# Edzzanine_Console.net
KiCad netlist of a schematic drawn in EAGLE
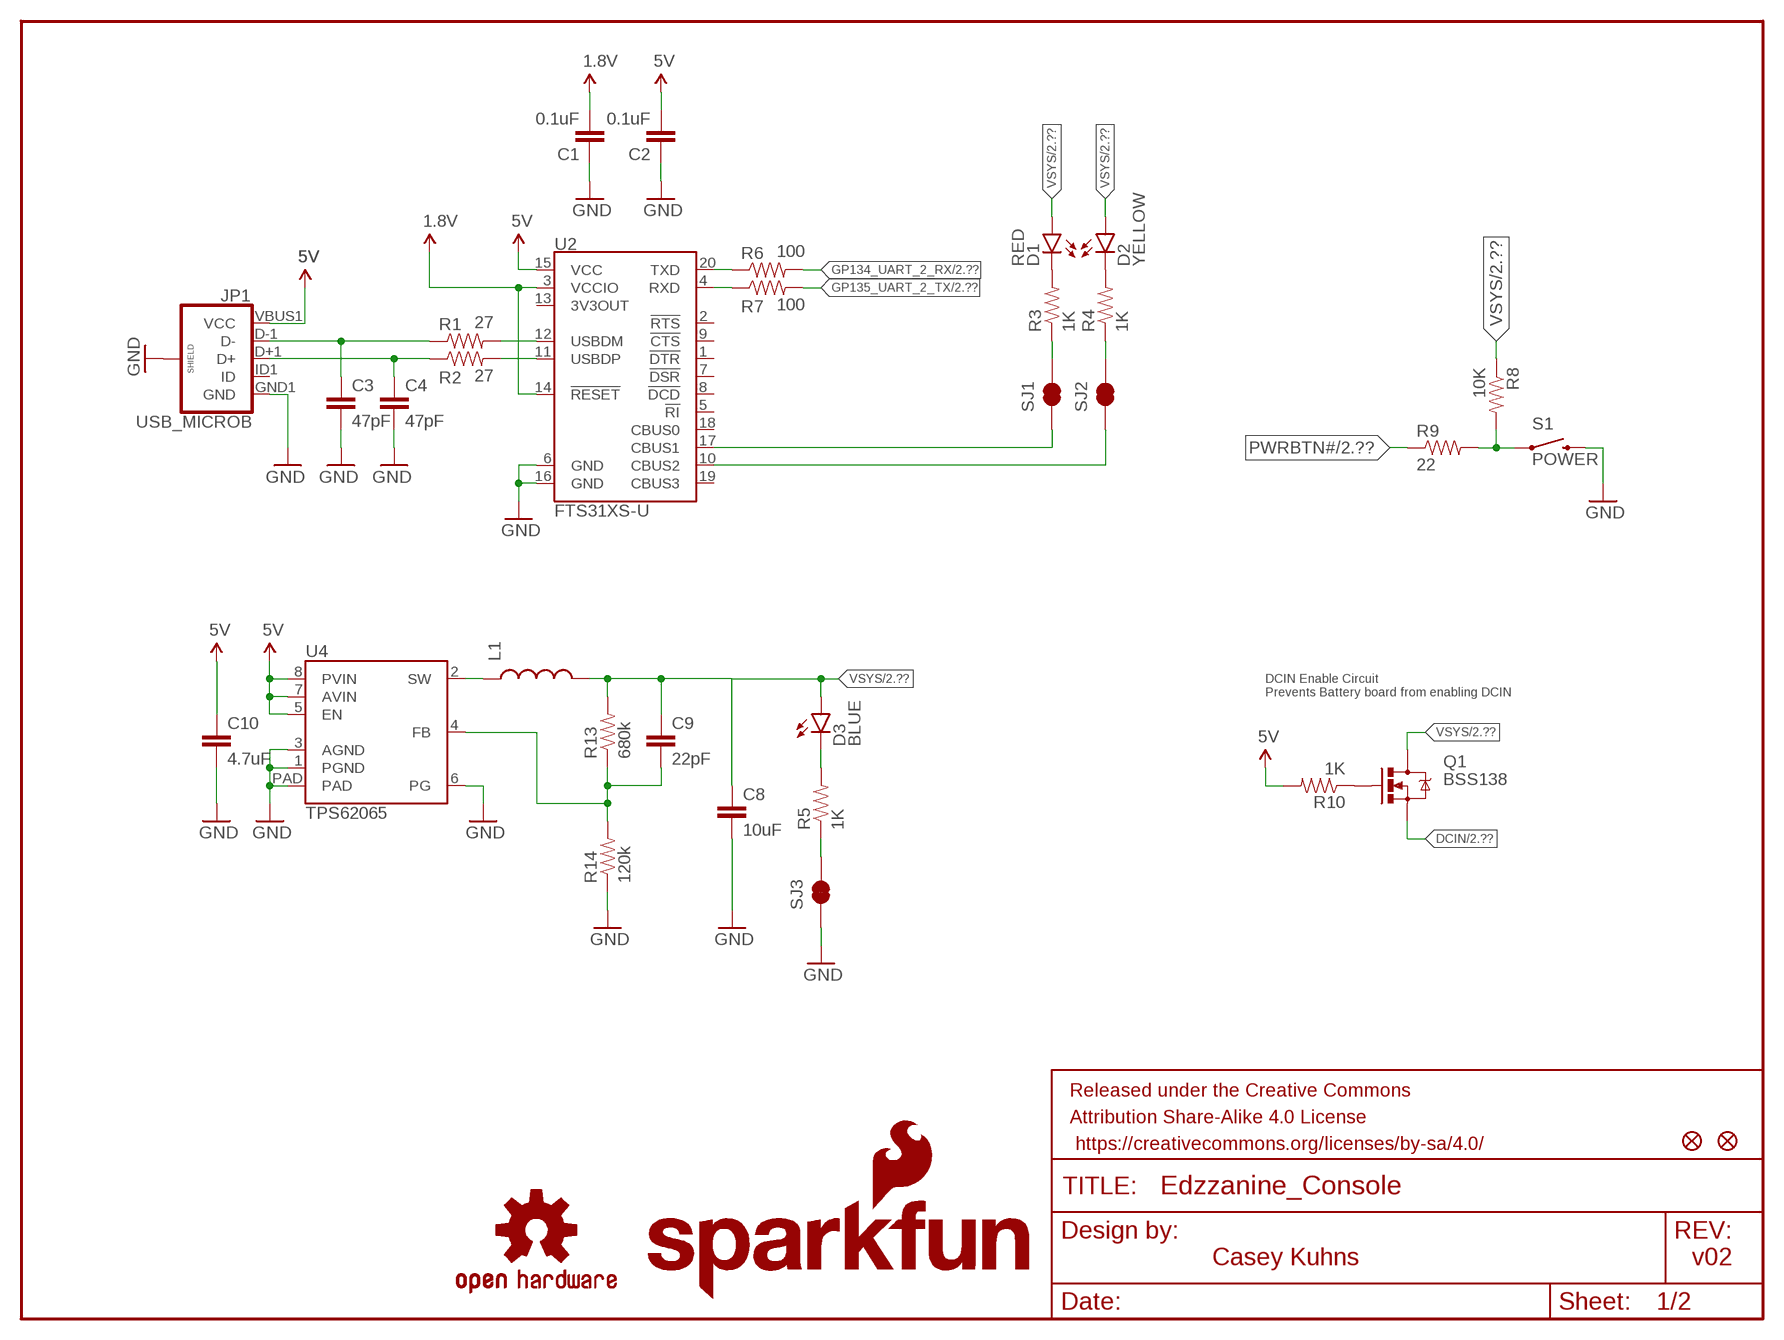
[diagram p0: schematic, sheet 1]
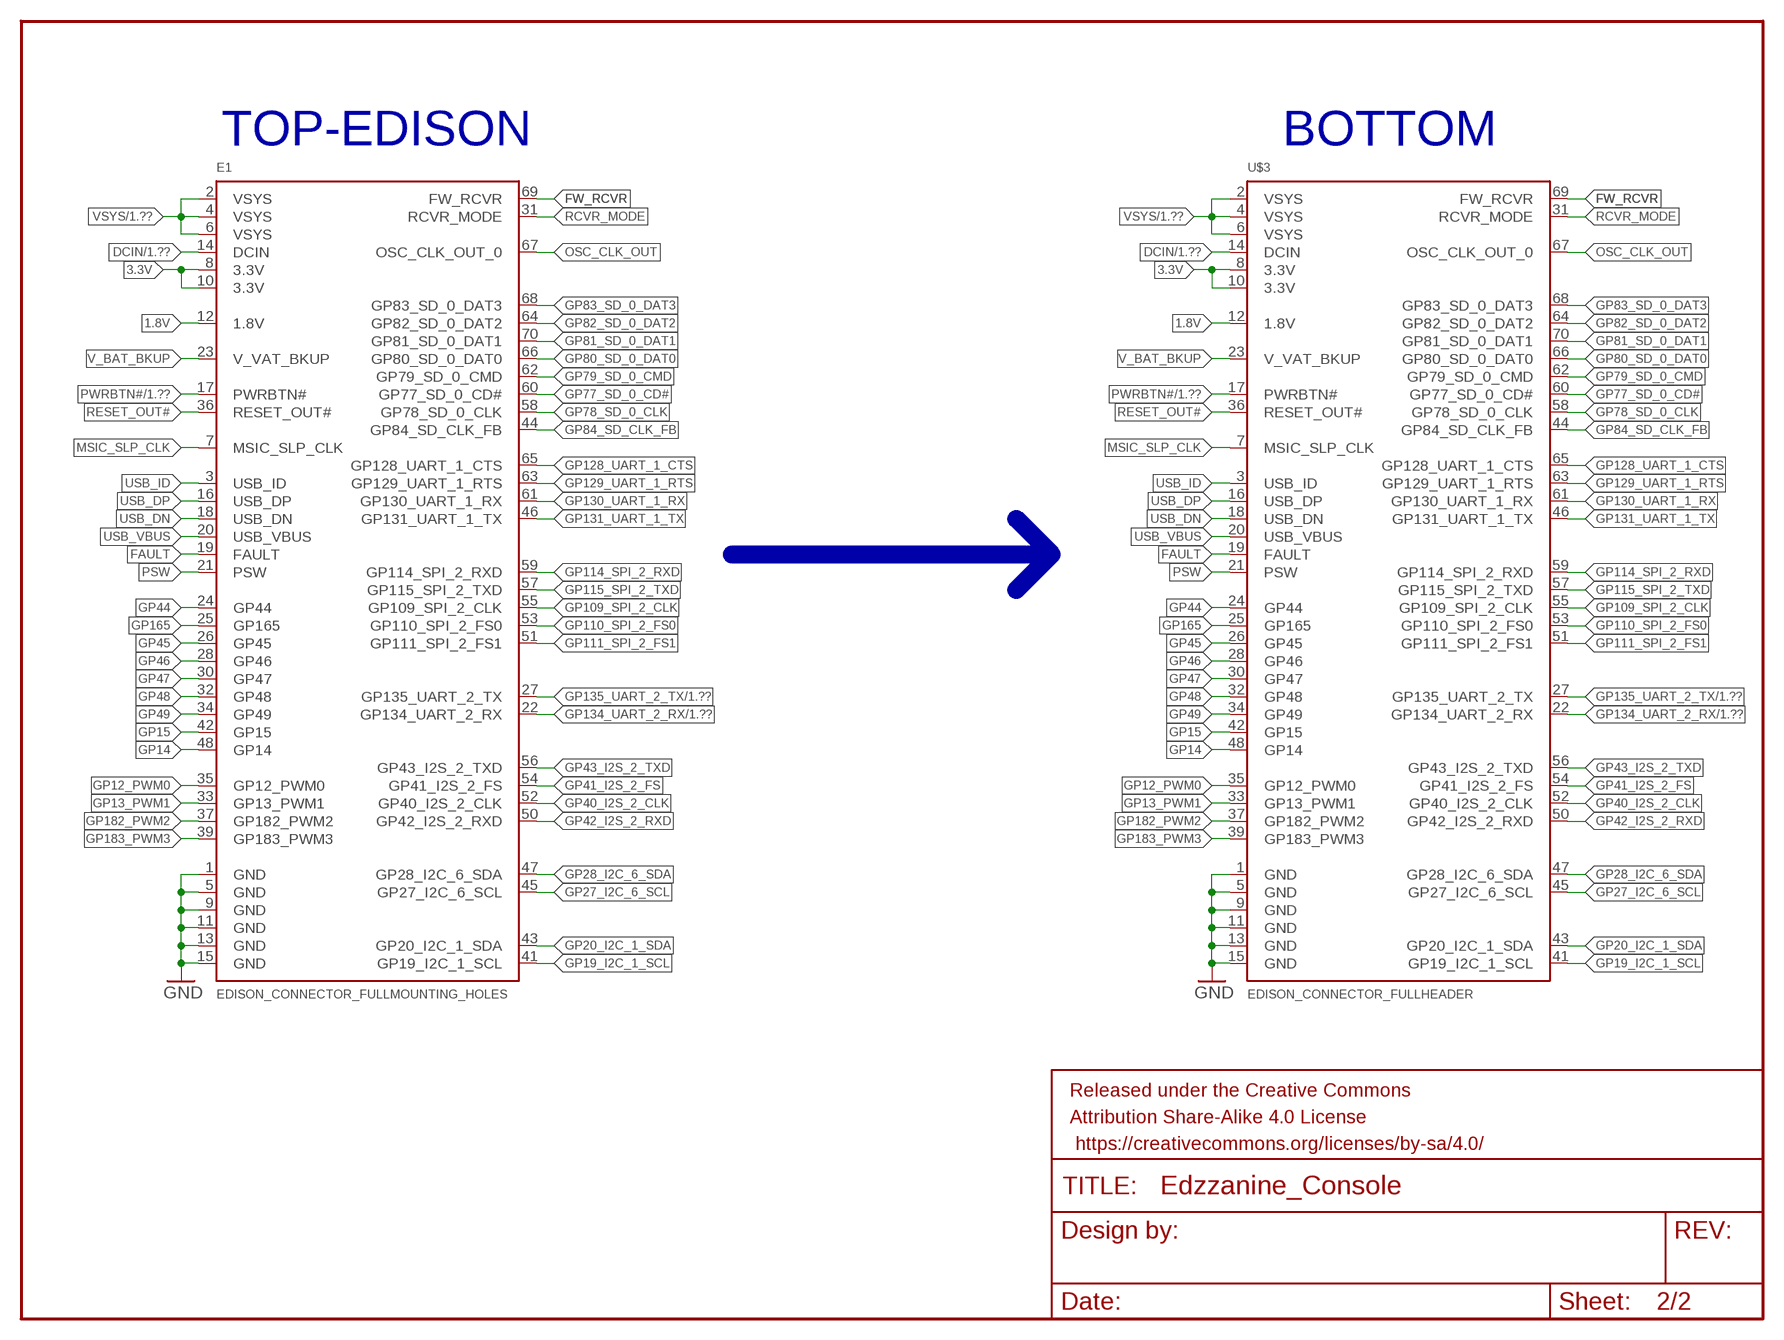
[diagram p1: schematic, sheet 2]

(export (version "E")
  (design (tool "Eeschema 10.0.6"))
  (components
    (comp (ref "E1")
      (value "EDISON_CONNECTOR_FULLMOUNTING_HOLES")
      (footprint "eagle-import:EDISON_DAUGHTER")
      (libsource (lib "eagle-import") (part "EDISON_CONNECTOR_FULLMOUNTING_HOLES"))
    )
    (comp (ref "FRAME2")
      (value "FRAME-LETTER")
      (footprint "eagle-import:CREATIVE_COMMONS")
      (libsource (lib "eagle-import") (part "FRAME-LETTER"))
    )
    (comp (ref "U$3")
      (value "EDISON_CONNECTOR_FULLHEADER")
      (footprint "eagle-import:DF40C-70DP-0.4(51)")
      (libsource (lib "eagle-import") (part "EDISON_CONNECTOR_FULLHEADER"))
    )
    (comp (ref "C1")
      (value "0.1uF")
      (footprint "eagle-import:0603-CAP")
      (libsource (lib "eagle-import") (part "0.1UF-25V-5%(0603)"))
    )
    (comp (ref "C2")
      (value "0.1uF")
      (footprint "eagle-import:0603-CAP")
      (libsource (lib "eagle-import") (part "0.1UF-25V-5%(0603)"))
    )
    (comp (ref "C3")
      (value "47pF")
      (footprint "eagle-import:0603-CAP")
      (libsource (lib "eagle-import") (part "47PF-50V-5%(0603)"))
    )
    (comp (ref "C4")
      (value "47pF")
      (footprint "eagle-import:0603-CAP")
      (libsource (lib "eagle-import") (part "47PF-50V-5%(0603)"))
    )
    (comp (ref "C8")
      (value "10uF")
      (footprint "eagle-import:1206")
      (libsource (lib "eagle-import") (part "10UF-6.3V-20%(1206)"))
    )
    (comp (ref "C9")
      (value "22pF")
      (footprint "eagle-import:0603-CAP")
      (libsource (lib "eagle-import") (part "22PF-50V-5%(0603)"))
    )
    (comp (ref "C10")
      (value "4.7uF")
      (footprint "eagle-import:0603-CAP")
      (libsource (lib "eagle-import") (part "4.7UF-6.3V-10%(0603)0603"))
    )
    (comp (ref "D1")
      (value "RED")
      (footprint "eagle-import:LED-0603")
      (libsource (lib "eagle-import") (part "LED-RED0603"))
    )
    (comp (ref "D2")
      (value "YELLOW")
      (footprint "eagle-import:LED-0603")
      (libsource (lib "eagle-import") (part "LED-YELLOW0603"))
    )
    (comp (ref "D3")
      (value "BLUE")
      (footprint "eagle-import:LED-0603")
      (libsource (lib "eagle-import") (part "LED-BLUE0603"))
    )
    (comp (ref "FID1")
      (value "FIDUCIAL1X2")
      (footprint "eagle-import:FIDUCIAL-1X2")
      (libsource (lib "eagle-import") (part "FIDUCIAL1X2"))
    )
    (comp (ref "FID2")
      (value "FIDUCIAL1X2")
      (footprint "eagle-import:FIDUCIAL-1X2")
      (libsource (lib "eagle-import") (part "FIDUCIAL1X2"))
    )
    (comp (ref "FRAME1")
      (value "FRAME-LETTER")
      (footprint "eagle-import:CREATIVE_COMMONS")
      (libsource (lib "eagle-import") (part "FRAME-LETTER"))
    )
    (comp (ref "JP1")
      (value "USB_MICROB")
      (footprint "eagle-import:USB-B-MICRO-SMD_V03")
      (libsource (lib "eagle-import") (part "USB_MICROB_PLUGCONN-11752"))
    )
    (comp (ref "L1")
      (value "INDUCTOR")
      (footprint "eagle-import:INDUCTOR-SRP4020")
      (libsource (lib "eagle-import") (part "INDUCTOR"))
    )
    (comp (ref "LOGO1")
      (value "SFE_LOGO_NAME_FLAME.1_INCH")
      (footprint "eagle-import:SFE_LOGO_NAME_FLAME_.1")
      (libsource (lib "eagle-import") (part "SFE_LOGO_NAME_FLAME.1_INCH"))
    )
    (comp (ref "LOGO4")
      (value "OSHW-LOGOS")
      (footprint "eagle-import:OSHW-LOGO-S")
      (libsource (lib "eagle-import") (part "OSHW-LOGOS"))
    )
    (comp (ref "Q1")
      (value "BSS138")
      (footprint "eagle-import:SOT23-3")
      (libsource (lib "eagle-import") (part "MOSFET-NCHANNELBSS138"))
    )
    (comp (ref "R1")
      (value "27")
      (footprint "eagle-import:0603")
      (libsource (lib "eagle-import") (part "27OHM1/10W1%(0603)"))
    )
    (comp (ref "R2")
      (value "27")
      (footprint "eagle-import:0603")
      (libsource (lib "eagle-import") (part "27OHM1/10W1%(0603)"))
    )
    (comp (ref "R3")
      (value "1K")
      (footprint "eagle-import:0603-RES")
      (libsource (lib "eagle-import") (part "1KOHM1/10W1%(0603)"))
    )
    (comp (ref "R4")
      (value "1K")
      (footprint "eagle-import:0603-RES")
      (libsource (lib "eagle-import") (part "1KOHM1/10W1%(0603)"))
    )
    (comp (ref "R5")
      (value "1K")
      (footprint "eagle-import:0603-RES")
      (libsource (lib "eagle-import") (part "1KOHM1/10W1%(0603)"))
    )
    (comp (ref "R6")
      (value "100")
      (footprint "eagle-import:0603-RES")
      (libsource (lib "eagle-import") (part "100OHM1/10W1%(0603)"))
    )
    (comp (ref "R7")
      (value "100")
      (footprint "eagle-import:0603-RES")
      (libsource (lib "eagle-import") (part "100OHM1/10W1%(0603)"))
    )
    (comp (ref "R8")
      (value "10K")
      (footprint "eagle-import:0603-RES")
      (libsource (lib "eagle-import") (part "10KOHM1/10W1%(0603)0603"))
    )
    (comp (ref "R9")
      (value "22")
      (footprint "eagle-import:0603-RES")
      (libsource (lib "eagle-import") (part "22OHM1/10W1%(0603)"))
    )
    (comp (ref "R10")
      (value "1K")
      (footprint "eagle-import:0603-RES")
      (libsource (lib "eagle-import") (part "1KOHM1/10W1%(0603)"))
    )
    (comp (ref "R13")
      (value "680k")
      (footprint "eagle-import:0603-RES")
      (libsource (lib "eagle-import") (part "RESISTOR0603"))
    )
    (comp (ref "R14")
      (value "120k")
      (footprint "eagle-import:0603-RES")
      (libsource (lib "eagle-import") (part "RESISTOR0603"))
    )
    (comp (ref "S1")
      (value "POWER")
      (footprint "eagle-import:TACTILE_SWITCH-SMD-RIGHT-ANGLE")
      (libsource (lib "eagle-import") (part "SWITCH-MOMENTARY-2TACTILE-SWITCH-SMD-RIGHT-ANGLE"))
    )
    (comp (ref "SJ1")
      (value "JUMPER-PAD-2-NC_BY_TRACE")
      (footprint "eagle-import:PAD-JUMPER-2-NC_BY_TRACE_YES_SILK")
      (libsource (lib "eagle-import") (part "JUMPER-PAD-2-NC_BY_TRACE"))
    )
    (comp (ref "SJ2")
      (value "JUMPER-PAD-2-NC_BY_TRACE")
      (footprint "eagle-import:PAD-JUMPER-2-NC_BY_TRACE_YES_SILK")
      (libsource (lib "eagle-import") (part "JUMPER-PAD-2-NC_BY_TRACE"))
    )
    (comp (ref "SJ3")
      (value "JUMPER-PAD-2-NC_BY_TRACE")
      (footprint "eagle-import:PAD-JUMPER-2-NC_BY_TRACE_YES_SILK")
      (libsource (lib "eagle-import") (part "JUMPER-PAD-2-NC_BY_TRACE"))
    )
    (comp (ref "U2")
      (value "FTS31XS-U")
      (footprint "eagle-import:SSOP20_L")
      (libsource (lib "eagle-import") (part "FT231XS"))
    )
    (comp (ref "U4")
      (value "TPS62065")
      (footprint "eagle-import:WSON-8-PAD")
      (libsource (lib "eagle-import") (part "TPS62065"))
    )
  )
  (nets
    (net (code "1") (name "1.8V") (class "Default")
      (node (ref "C1") (pin "2") (pinfunction "2_2") (pintype "passive"))
      (node (ref "E1") (pin "12") (pinfunction "1.8V_12") (pintype "bidirectional"))
      (node (ref "U$3") (pin "12") (pinfunction "1.8V_12") (pintype "bidirectional"))
      (node (ref "U2") (pin "14") (pinfunction "~{RESET}_14") (pintype "bidirectional"))
      (node (ref "U2") (pin "3") (pinfunction "VCCIO_3") (pintype "bidirectional"))
    )
    (net (code "2") (name "3.3V") (class "Default")
      (node (ref "E1") (pin "10") (pinfunction "3.3V_10") (pintype "bidirectional"))
      (node (ref "E1") (pin "8") (pinfunction "3.3V_8") (pintype "bidirectional"))
      (node (ref "U$3") (pin "10") (pinfunction "3.3V_10") (pintype "bidirectional"))
      (node (ref "U$3") (pin "8") (pinfunction "3.3V_8") (pintype "bidirectional"))
    )
    (net (code "3") (name "5V") (class "Default")
      (node (ref "C10") (pin "1") (pinfunction "1_1") (pintype "passive"))
      (node (ref "C2") (pin "2") (pinfunction "2_2") (pintype "passive"))
      (node (ref "JP1") (pin "VBUS1") (pinfunction "VCC_VBUS1") (pintype "bidirectional"))
      (node (ref "R10") (pin "2") (pinfunction "2_2") (pintype "passive"))
      (node (ref "U2") (pin "15") (pinfunction "VCC_15") (pintype "bidirectional"))
      (node (ref "U4") (pin "5") (pinfunction "EN_5") (pintype "bidirectional"))
      (node (ref "U4") (pin "7") (pinfunction "AVIN_7") (pintype "bidirectional"))
      (node (ref "U4") (pin "8") (pinfunction "PVIN_8") (pintype "bidirectional"))
    )
    (net (code "4") (name "DCIN") (class "Default")
      (node (ref "E1") (pin "14") (pinfunction "DCIN_14") (pintype "bidirectional"))
      (node (ref "Q1") (pin "2") (pinfunction "S_2") (pintype "passive"))
      (node (ref "U$3") (pin "14") (pinfunction "DCIN_14") (pintype "bidirectional"))
    )
    (net (code "5") (name "FAULT") (class "Default")
      (node (ref "E1") (pin "19") (pinfunction "FAULT_19") (pintype "bidirectional"))
      (node (ref "U$3") (pin "19") (pinfunction "FAULT_19") (pintype "bidirectional"))
    )
    (net (code "6") (name "FW_RCVR") (class "Default")
      (node (ref "E1") (pin "69") (pinfunction "FW_RCVR_69") (pintype "bidirectional"))
      (node (ref "U$3") (pin "69") (pinfunction "FW_RCVR_69") (pintype "bidirectional"))
    )
    (net (code "7") (name "GND") (class "Default")
      (node (ref "C1") (pin "1") (pinfunction "1_1") (pintype "passive"))
      (node (ref "C10") (pin "2") (pinfunction "2_2") (pintype "passive"))
      (node (ref "C2") (pin "1") (pinfunction "1_1") (pintype "passive"))
      (node (ref "C3") (pin "2") (pinfunction "2_2") (pintype "passive"))
      (node (ref "C4") (pin "2") (pinfunction "2_2") (pintype "passive"))
      (node (ref "C8") (pin "2") (pinfunction "2_2") (pintype "passive"))
      (node (ref "E1") (pin "1") (pinfunction "GND_1") (pintype "bidirectional"))
      (node (ref "E1") (pin "11") (pinfunction "GND_11") (pintype "bidirectional"))
      (node (ref "E1") (pin "13") (pinfunction "GND_13") (pintype "bidirectional"))
      (node (ref "E1") (pin "15") (pinfunction "GND_15") (pintype "bidirectional"))
      (node (ref "E1") (pin "5") (pinfunction "GND_5") (pintype "bidirectional"))
      (node (ref "E1") (pin "9") (pinfunction "GND_9") (pintype "bidirectional"))
      (node (ref "JP1") (pin "GND1") (pinfunction "GND_GND1") (pintype "bidirectional"))
      (node (ref "JP1") (pin "SHIELD1") (pinfunction "SHIELD_SHIELD1") (pintype "bidirectional"))
      (node (ref "JP1") (pin "SHIELD2") (pinfunction "SHIELD_SHIELD2") (pintype "bidirectional"))
      (node (ref "JP1") (pin "SHIELD3") (pinfunction "SHIELD_SHIELD3") (pintype "bidirectional"))
      (node (ref "R14") (pin "1") (pinfunction "1_1") (pintype "passive"))
      (node (ref "S1") (pin "2") (pinfunction "2_2") (pintype "passive"))
      (node (ref "SJ3") (pin "1") (pinfunction "1_1") (pintype "passive"))
      (node (ref "U$3") (pin "1") (pinfunction "GND_1") (pintype "bidirectional"))
      (node (ref "U$3") (pin "11") (pinfunction "GND_11") (pintype "bidirectional"))
      (node (ref "U$3") (pin "13") (pinfunction "GND_13") (pintype "bidirectional"))
      (node (ref "U$3") (pin "15") (pinfunction "GND_15") (pintype "bidirectional"))
      (node (ref "U$3") (pin "5") (pinfunction "GND_5") (pintype "bidirectional"))
      (node (ref "U$3") (pin "9") (pinfunction "GND_9") (pintype "bidirectional"))
      (node (ref "U2") (pin "16") (pinfunction "GND_16") (pintype "bidirectional"))
      (node (ref "U2") (pin "6") (pinfunction "GND_6") (pintype "bidirectional"))
      (node (ref "U4") (pin "1") (pinfunction "PGND_1") (pintype "bidirectional"))
      (node (ref "U4") (pin "3") (pinfunction "AGND_3") (pintype "bidirectional"))
      (node (ref "U4") (pin "6") (pinfunction "PG_6") (pintype "bidirectional"))
      (node (ref "U4") (pin "PAD") (pinfunction "PAD_PAD") (pintype "bidirectional"))
    )
    (net (code "8") (name "GP12_PWM0") (class "Default")
      (node (ref "E1") (pin "35") (pinfunction "GP12_PWM0_35") (pintype "bidirectional"))
      (node (ref "U$3") (pin "35") (pinfunction "GP12_PWM0_35") (pintype "bidirectional"))
    )
    (net (code "9") (name "GP13_PWM1") (class "Default")
      (node (ref "E1") (pin "33") (pinfunction "GP13_PWM1_33") (pintype "bidirectional"))
      (node (ref "U$3") (pin "33") (pinfunction "GP13_PWM1_33") (pintype "bidirectional"))
    )
    (net (code "10") (name "GP14") (class "Default")
      (node (ref "E1") (pin "48") (pinfunction "GP14_48") (pintype "bidirectional"))
      (node (ref "U$3") (pin "48") (pinfunction "GP14_48") (pintype "bidirectional"))
    )
    (net (code "11") (name "GP15") (class "Default")
      (node (ref "E1") (pin "42") (pinfunction "GP15_42") (pintype "bidirectional"))
      (node (ref "U$3") (pin "42") (pinfunction "GP15_42") (pintype "bidirectional"))
    )
    (net (code "12") (name "GP19_I2C_1_SCL") (class "Default")
      (node (ref "E1") (pin "41") (pinfunction "GP19_I2C_1_SCL_41") (pintype "bidirectional"))
      (node (ref "U$3") (pin "41") (pinfunction "GP19_I2C_1_SCL_41") (pintype "bidirectional"))
    )
    (net (code "13") (name "GP20_I2C_1_SDA") (class "Default")
      (node (ref "E1") (pin "43") (pinfunction "GP20_I2C_1_SDA_43") (pintype "bidirectional"))
      (node (ref "U$3") (pin "43") (pinfunction "GP20_I2C_1_SDA_43") (pintype "bidirectional"))
    )
    (net (code "14") (name "GP27_I2C_6_SCL") (class "Default")
      (node (ref "E1") (pin "45") (pinfunction "GP27_I2C_6_SCL_45") (pintype "bidirectional"))
      (node (ref "U$3") (pin "45") (pinfunction "GP27_I2C_6_SCL_45") (pintype "bidirectional"))
    )
    (net (code "15") (name "GP28_I2C_6_SDA") (class "Default")
      (node (ref "E1") (pin "47") (pinfunction "GP28_I2C_6_SDA_47") (pintype "bidirectional"))
      (node (ref "U$3") (pin "47") (pinfunction "GP28_I2C_6_SDA_47") (pintype "bidirectional"))
    )
    (net (code "16") (name "GP40_I2S_2_CLK") (class "Default")
      (node (ref "E1") (pin "52") (pinfunction "GP40_I2S_2_CLK_52") (pintype "bidirectional"))
      (node (ref "U$3") (pin "52") (pinfunction "GP40_I2S_2_CLK_52") (pintype "bidirectional"))
    )
    (net (code "17") (name "GP41_I2S_2_FS") (class "Default")
      (node (ref "E1") (pin "54") (pinfunction "GP41_I2S_2_FS_54") (pintype "bidirectional"))
      (node (ref "U$3") (pin "54") (pinfunction "GP41_I2S_2_FS_54") (pintype "bidirectional"))
    )
    (net (code "18") (name "GP42_I2S_2_RXD") (class "Default")
      (node (ref "E1") (pin "50") (pinfunction "GP42_I2S_2_RXD_50") (pintype "bidirectional"))
      (node (ref "U$3") (pin "50") (pinfunction "GP42_I2S_2_RXD_50") (pintype "bidirectional"))
    )
    (net (code "19") (name "GP43_I2S_2_TXD") (class "Default")
      (node (ref "E1") (pin "56") (pinfunction "GP43_I2S_2_TXD_56") (pintype "bidirectional"))
      (node (ref "U$3") (pin "56") (pinfunction "GP43_I2S_2_TXD_56") (pintype "bidirectional"))
    )
    (net (code "20") (name "GP44") (class "Default")
      (node (ref "E1") (pin "24") (pinfunction "GP44_24") (pintype "bidirectional"))
      (node (ref "U$3") (pin "24") (pinfunction "GP44_24") (pintype "bidirectional"))
    )
    (net (code "21") (name "GP45") (class "Default")
      (node (ref "E1") (pin "26") (pinfunction "GP45_26") (pintype "bidirectional"))
      (node (ref "U$3") (pin "26") (pinfunction "GP45_26") (pintype "bidirectional"))
    )
    (net (code "22") (name "GP46") (class "Default")
      (node (ref "E1") (pin "28") (pinfunction "GP46_28") (pintype "bidirectional"))
      (node (ref "U$3") (pin "28") (pinfunction "GP46_28") (pintype "bidirectional"))
    )
    (net (code "23") (name "GP47") (class "Default")
      (node (ref "E1") (pin "30") (pinfunction "GP47_30") (pintype "bidirectional"))
      (node (ref "U$3") (pin "30") (pinfunction "GP47_30") (pintype "bidirectional"))
    )
    (net (code "24") (name "GP48") (class "Default")
      (node (ref "E1") (pin "32") (pinfunction "GP48_32") (pintype "bidirectional"))
      (node (ref "U$3") (pin "32") (pinfunction "GP48_32") (pintype "bidirectional"))
    )
    (net (code "25") (name "GP49") (class "Default")
      (node (ref "E1") (pin "34") (pinfunction "GP49_34") (pintype "bidirectional"))
      (node (ref "U$3") (pin "34") (pinfunction "GP49_34") (pintype "bidirectional"))
    )
    (net (code "26") (name "GP77_SD_0_CD#") (class "Default")
      (node (ref "E1") (pin "60") (pinfunction "GP77_SD_0_CD#_60") (pintype "bidirectional"))
      (node (ref "U$3") (pin "60") (pinfunction "GP77_SD_0_CD#_60") (pintype "bidirectional"))
    )
    (net (code "27") (name "GP78_SD_0_CLK") (class "Default")
      (node (ref "E1") (pin "58") (pinfunction "GP78_SD_0_CLK_58") (pintype "bidirectional"))
      (node (ref "U$3") (pin "58") (pinfunction "GP78_SD_0_CLK_58") (pintype "bidirectional"))
    )
    (net (code "28") (name "GP79_SD_0_CMD") (class "Default")
      (node (ref "E1") (pin "62") (pinfunction "GP79_SD_0_CMD_62") (pintype "bidirectional"))
      (node (ref "U$3") (pin "62") (pinfunction "GP79_SD_0_CMD_62") (pintype "bidirectional"))
    )
    (net (code "29") (name "GP80_SD_0_DAT0") (class "Default")
      (node (ref "E1") (pin "66") (pinfunction "GP80_SD_0_DAT0_66") (pintype "bidirectional"))
      (node (ref "U$3") (pin "66") (pinfunction "GP80_SD_0_DAT0_66") (pintype "bidirectional"))
    )
    (net (code "30") (name "GP81_SD_0_DAT1") (class "Default")
      (node (ref "E1") (pin "70") (pinfunction "GP81_SD_0_DAT1_70") (pintype "bidirectional"))
      (node (ref "U$3") (pin "70") (pinfunction "GP81_SD_0_DAT1_70") (pintype "bidirectional"))
    )
    (net (code "31") (name "GP82_SD_0_DAT2") (class "Default")
      (node (ref "E1") (pin "64") (pinfunction "GP82_SD_0_DAT2_64") (pintype "bidirectional"))
      (node (ref "U$3") (pin "64") (pinfunction "GP82_SD_0_DAT2_64") (pintype "bidirectional"))
    )
    (net (code "32") (name "GP83_SD_0_DAT3") (class "Default")
      (node (ref "E1") (pin "68") (pinfunction "GP83_SD_0_DAT3_68") (pintype "bidirectional"))
      (node (ref "U$3") (pin "68") (pinfunction "GP83_SD_0_DAT3_68") (pintype "bidirectional"))
    )
    (net (code "33") (name "GP84_SD_CLK_FB") (class "Default")
      (node (ref "E1") (pin "44") (pinfunction "GP84_SD_CLK_FB_44") (pintype "bidirectional"))
      (node (ref "U$3") (pin "44") (pinfunction "GP84_SD_CLK_FB_44") (pintype "bidirectional"))
    )
    (net (code "34") (name "GP109_SPI_2_CLK") (class "Default")
      (node (ref "E1") (pin "55") (pinfunction "GP109_SPI_2_CLK_55") (pintype "bidirectional"))
      (node (ref "U$3") (pin "55") (pinfunction "GP109_SPI_2_CLK_55") (pintype "bidirectional"))
    )
    (net (code "35") (name "GP110_SPI_2_FS0") (class "Default")
      (node (ref "E1") (pin "53") (pinfunction "GP110_SPI_2_FS0_53") (pintype "bidirectional"))
      (node (ref "U$3") (pin "53") (pinfunction "GP110_SPI_2_FS0_53") (pintype "bidirectional"))
    )
    (net (code "36") (name "GP111_SPI_2_FS1") (class "Default")
      (node (ref "E1") (pin "51") (pinfunction "GP111_SPI_2_FS1_51") (pintype "bidirectional"))
      (node (ref "U$3") (pin "51") (pinfunction "GP111_SPI_2_FS1_51") (pintype "bidirectional"))
    )
    (net (code "37") (name "GP114_SPI_2_RXD") (class "Default")
      (node (ref "E1") (pin "59") (pinfunction "GP114_SPI_2_RXD_59") (pintype "bidirectional"))
      (node (ref "U$3") (pin "59") (pinfunction "GP114_SPI_2_RXD_59") (pintype "bidirectional"))
    )
    (net (code "38") (name "GP115_SPI_2_TXD") (class "Default")
      (node (ref "E1") (pin "57") (pinfunction "GP115_SPI_2_TXD_57") (pintype "bidirectional"))
      (node (ref "U$3") (pin "57") (pinfunction "GP115_SPI_2_TXD_57") (pintype "bidirectional"))
    )
    (net (code "39") (name "GP128_UART_1_CTS") (class "Default")
      (node (ref "E1") (pin "65") (pinfunction "GP128_UART_1_CTS_65") (pintype "bidirectional"))
      (node (ref "U$3") (pin "65") (pinfunction "GP128_UART_1_CTS_65") (pintype "bidirectional"))
    )
    (net (code "40") (name "GP129_UART_1_RTS") (class "Default")
      (node (ref "E1") (pin "63") (pinfunction "GP129_UART_1_RTS_63") (pintype "bidirectional"))
      (node (ref "U$3") (pin "63") (pinfunction "GP129_UART_1_RTS_63") (pintype "bidirectional"))
    )
    (net (code "41") (name "GP130_UART_1_RX") (class "Default")
      (node (ref "E1") (pin "61") (pinfunction "GP130_UART_1_RX_61") (pintype "bidirectional"))
      (node (ref "U$3") (pin "61") (pinfunction "GP130_UART_1_RX_61") (pintype "bidirectional"))
    )
    (net (code "42") (name "GP131_UART_1_TX") (class "Default")
      (node (ref "E1") (pin "46") (pinfunction "GP131_UART_1_TX_46") (pintype "bidirectional"))
      (node (ref "U$3") (pin "46") (pinfunction "GP131_UART_1_TX_46") (pintype "bidirectional"))
    )
    (net (code "43") (name "GP134_UART_2_RX") (class "Default")
      (node (ref "E1") (pin "22") (pinfunction "GP134_UART_2_RX_22") (pintype "bidirectional"))
      (node (ref "R6") (pin "2") (pinfunction "2_2") (pintype "passive"))
      (node (ref "U$3") (pin "22") (pinfunction "GP134_UART_2_RX_22") (pintype "bidirectional"))
    )
    (net (code "44") (name "GP135_UART_2_TX") (class "Default")
      (node (ref "E1") (pin "27") (pinfunction "GP135_UART_2_TX_27") (pintype "bidirectional"))
      (node (ref "R7") (pin "2") (pinfunction "2_2") (pintype "passive"))
      (node (ref "U$3") (pin "27") (pinfunction "GP135_UART_2_TX_27") (pintype "bidirectional"))
    )
    (net (code "45") (name "GP165") (class "Default")
      (node (ref "E1") (pin "25") (pinfunction "GP165_25") (pintype "bidirectional"))
      (node (ref "U$3") (pin "25") (pinfunction "GP165_25") (pintype "bidirectional"))
    )
    (net (code "46") (name "GP182_PWM2") (class "Default")
      (node (ref "E1") (pin "37") (pinfunction "GP182_PWM2_37") (pintype "bidirectional"))
      (node (ref "U$3") (pin "37") (pinfunction "GP182_PWM2_37") (pintype "bidirectional"))
    )
    (net (code "47") (name "GP183_PWM3") (class "Default")
      (node (ref "E1") (pin "39") (pinfunction "GP183_PWM3_39") (pintype "bidirectional"))
      (node (ref "U$3") (pin "39") (pinfunction "GP183_PWM3_39") (pintype "bidirectional"))
    )
    (net (code "48") (name "MSIC_SLP_CLK") (class "Default")
      (node (ref "E1") (pin "7") (pinfunction "MSIC_SLP_CLK_7") (pintype "bidirectional"))
      (node (ref "U$3") (pin "7") (pinfunction "MSIC_SLP_CLK_7") (pintype "bidirectional"))
    )
    (net (code "49") (name "Net-(D1-PadC)") (class "Default")
      (node (ref "D1") (pin "C") (pinfunction "C_C") (pintype "passive"))
      (node (ref "R3") (pin "2") (pinfunction "2_2") (pintype "passive"))
    )
    (net (code "50") (name "Net-(D2-PadC)") (class "Default")
      (node (ref "D2") (pin "C") (pinfunction "C_C") (pintype "passive"))
      (node (ref "R4") (pin "2") (pinfunction "2_2") (pintype "passive"))
    )
    (net (code "51") (name "Net-(D3-PadC)") (class "Default")
      (node (ref "D3") (pin "C") (pinfunction "C_C") (pintype "passive"))
      (node (ref "R5") (pin "2") (pinfunction "2_2") (pintype "passive"))
    )
    (net (code "52") (name "Net-(JP1-D+)") (class "Default")
      (node (ref "C4") (pin "1") (pinfunction "1_1") (pintype "passive"))
      (node (ref "JP1") (pin "D+1") (pinfunction "D+_D+1") (pintype "bidirectional"))
      (node (ref "R2") (pin "1") (pinfunction "1_1") (pintype "passive"))
    )
    (net (code "53") (name "Net-(JP1-D-)") (class "Default")
      (node (ref "C3") (pin "1") (pinfunction "1_1") (pintype "passive"))
      (node (ref "JP1") (pin "D-1") (pinfunction "D-_D-1") (pintype "bidirectional"))
      (node (ref "R1") (pin "1") (pinfunction "1_1") (pintype "passive"))
    )
    (net (code "54") (name "Net-(L1-1)") (class "Default")
      (node (ref "L1") (pin "P$1") (pinfunction "1_P$1") (pintype "passive"))
      (node (ref "U4") (pin "2") (pinfunction "SW_2") (pintype "bidirectional"))
    )
    (net (code "55") (name "Net-(Q1-G)") (class "Default")
      (node (ref "Q1") (pin "1") (pinfunction "G_1") (pintype "passive"))
      (node (ref "R10") (pin "1") (pinfunction "1_1") (pintype "passive"))
    )
    (net (code "56") (name "Net-(R3-Pad1)") (class "Default")
      (node (ref "R3") (pin "1") (pinfunction "1_1") (pintype "passive"))
      (node (ref "SJ1") (pin "2") (pinfunction "2_2") (pintype "passive"))
    )
    (net (code "57") (name "Net-(R4-Pad1)") (class "Default")
      (node (ref "R4") (pin "1") (pinfunction "1_1") (pintype "passive"))
      (node (ref "SJ2") (pin "2") (pinfunction "2_2") (pintype "passive"))
    )
    (net (code "58") (name "Net-(R5-Pad1)") (class "Default")
      (node (ref "R5") (pin "1") (pinfunction "1_1") (pintype "passive"))
      (node (ref "SJ3") (pin "2") (pinfunction "2_2") (pintype "passive"))
    )
    (net (code "59") (name "Net-(R8-Pad2)") (class "Default")
      (node (ref "R8") (pin "2") (pinfunction "2_2") (pintype "passive"))
      (node (ref "R9") (pin "2") (pinfunction "2_2") (pintype "passive"))
      (node (ref "S1") (pin "1") (pinfunction "1_1") (pintype "passive"))
    )
    (net (code "60") (name "Net-(U2-CBUS1)") (class "Default")
      (node (ref "SJ1") (pin "1") (pinfunction "1_1") (pintype "passive"))
      (node (ref "U2") (pin "17") (pinfunction "CBUS1_17") (pintype "bidirectional"))
    )
    (net (code "61") (name "Net-(U2-CBUS2)") (class "Default")
      (node (ref "SJ2") (pin "1") (pinfunction "1_1") (pintype "passive"))
      (node (ref "U2") (pin "10") (pinfunction "CBUS2_10") (pintype "bidirectional"))
    )
    (net (code "62") (name "Net-(U2-RXD)") (class "Default")
      (node (ref "R7") (pin "1") (pinfunction "1_1") (pintype "passive"))
      (node (ref "U2") (pin "4") (pinfunction "RXD_4") (pintype "bidirectional"))
    )
    (net (code "63") (name "Net-(U2-TXD)") (class "Default")
      (node (ref "R6") (pin "1") (pinfunction "1_1") (pintype "passive"))
      (node (ref "U2") (pin "20") (pinfunction "TXD_20") (pintype "bidirectional"))
    )
    (net (code "64") (name "Net-(U2-USBDM)") (class "Default")
      (node (ref "R1") (pin "2") (pinfunction "2_2") (pintype "passive"))
      (node (ref "U2") (pin "12") (pinfunction "USBDM_12") (pintype "bidirectional"))
    )
    (net (code "65") (name "Net-(U2-USBDP)") (class "Default")
      (node (ref "R2") (pin "2") (pinfunction "2_2") (pintype "passive"))
      (node (ref "U2") (pin "11") (pinfunction "USBDP_11") (pintype "bidirectional"))
    )
    (net (code "66") (name "Net-(U4-FB)") (class "Default")
      (node (ref "C9") (pin "2") (pinfunction "2_2") (pintype "passive"))
      (node (ref "R13") (pin "1") (pinfunction "1_1") (pintype "passive"))
      (node (ref "R14") (pin "2") (pinfunction "2_2") (pintype "passive"))
      (node (ref "U4") (pin "4") (pinfunction "FB_4") (pintype "bidirectional"))
    )
    (net (code "67") (name "OSC_CLK_OUT") (class "Default")
      (node (ref "E1") (pin "67") (pinfunction "OSC_CLK_OUT_0_67") (pintype "bidirectional"))
      (node (ref "U$3") (pin "67") (pinfunction "OSC_CLK_OUT_0_67") (pintype "bidirectional"))
    )
    (net (code "68") (name "PSW") (class "Default")
      (node (ref "E1") (pin "21") (pinfunction "PSW_21") (pintype "bidirectional"))
      (node (ref "U$3") (pin "21") (pinfunction "PSW_21") (pintype "bidirectional"))
    )
    (net (code "69") (name "PWRBTN#") (class "Default")
      (node (ref "E1") (pin "17") (pinfunction "PWRBTN#_17") (pintype "bidirectional"))
      (node (ref "R9") (pin "1") (pinfunction "1_1") (pintype "passive"))
      (node (ref "U$3") (pin "17") (pinfunction "PWRBTN#_17") (pintype "bidirectional"))
    )
    (net (code "70") (name "RCVR_MODE") (class "Default")
      (node (ref "E1") (pin "31") (pinfunction "RCVR_MODE_31") (pintype "bidirectional"))
      (node (ref "U$3") (pin "31") (pinfunction "RCVR_MODE_31") (pintype "bidirectional"))
    )
    (net (code "71") (name "RESET_OUT#") (class "Default")
      (node (ref "E1") (pin "36") (pinfunction "RESET_OUT#_36") (pintype "bidirectional"))
      (node (ref "U$3") (pin "36") (pinfunction "RESET_OUT#_36") (pintype "bidirectional"))
    )
    (net (code "72") (name "USB_DN") (class "Default")
      (node (ref "E1") (pin "18") (pinfunction "USB_DN_18") (pintype "bidirectional"))
      (node (ref "U$3") (pin "18") (pinfunction "USB_DN_18") (pintype "bidirectional"))
    )
    (net (code "73") (name "USB_DP") (class "Default")
      (node (ref "E1") (pin "16") (pinfunction "USB_DP_16") (pintype "bidirectional"))
      (node (ref "U$3") (pin "16") (pinfunction "USB_DP_16") (pintype "bidirectional"))
    )
    (net (code "74") (name "USB_ID") (class "Default")
      (node (ref "E1") (pin "3") (pinfunction "USB_ID_3") (pintype "bidirectional"))
      (node (ref "U$3") (pin "3") (pinfunction "USB_ID_3") (pintype "bidirectional"))
    )
    (net (code "75") (name "USB_VBUS") (class "Default")
      (node (ref "E1") (pin "20") (pinfunction "USB_VBUS_20") (pintype "bidirectional"))
      (node (ref "U$3") (pin "20") (pinfunction "USB_VBUS_20") (pintype "bidirectional"))
    )
    (net (code "76") (name "VSYS") (class "Default")
      (node (ref "C8") (pin "1") (pinfunction "1_1") (pintype "passive"))
      (node (ref "C9") (pin "1") (pinfunction "1_1") (pintype "passive"))
      (node (ref "D1") (pin "A") (pinfunction "A_A") (pintype "passive"))
      (node (ref "D2") (pin "A") (pinfunction "A_A") (pintype "passive"))
      (node (ref "D3") (pin "A") (pinfunction "A_A") (pintype "passive"))
      (node (ref "E1") (pin "2") (pinfunction "VSYS_2") (pintype "bidirectional"))
      (node (ref "E1") (pin "4") (pinfunction "VSYS_4") (pintype "bidirectional"))
      (node (ref "E1") (pin "6") (pinfunction "VSYS_6") (pintype "bidirectional"))
      (node (ref "L1") (pin "P$2") (pinfunction "2_P$2") (pintype "passive"))
      (node (ref "Q1") (pin "3") (pinfunction "D_3") (pintype "passive"))
      (node (ref "R13") (pin "2") (pinfunction "2_2") (pintype "passive"))
      (node (ref "R8") (pin "1") (pinfunction "1_1") (pintype "passive"))
      (node (ref "U$3") (pin "2") (pinfunction "VSYS_2") (pintype "bidirectional"))
      (node (ref "U$3") (pin "4") (pinfunction "VSYS_4") (pintype "bidirectional"))
      (node (ref "U$3") (pin "6") (pinfunction "VSYS_6") (pintype "bidirectional"))
    )
    (net (code "77") (name "V_BAT_BKUP") (class "Default")
      (node (ref "E1") (pin "23") (pinfunction "V_VAT_BKUP_23") (pintype "bidirectional"))
      (node (ref "U$3") (pin "23") (pinfunction "V_VAT_BKUP_23") (pintype "bidirectional"))
    )
    (net (code "78") (name "unconnected-(JP1-ID-PadID1)") (class "Default")
      (node (ref "JP1") (pin "ID1") (pinfunction "ID_ID1") (pintype "bidirectional"))
    )
    (net (code "79") (name "unconnected-(U2-3V3OUT-Pad13)") (class "Default")
      (node (ref "U2") (pin "13") (pinfunction "3V3OUT_13") (pintype "bidirectional"))
    )
    (net (code "80") (name "unconnected-(U2-CBUS0-Pad18)") (class "Default")
      (node (ref "U2") (pin "18") (pinfunction "CBUS0_18") (pintype "bidirectional"))
    )
    (net (code "81") (name "unconnected-(U2-CBUS3-Pad19)") (class "Default")
      (node (ref "U2") (pin "19") (pinfunction "CBUS3_19") (pintype "bidirectional"))
    )
    (net (code "82") (name "unconnected-(U2-~{CTS}-Pad9)") (class "Default")
      (node (ref "U2") (pin "9") (pinfunction "~{CTS}_9") (pintype "bidirectional"))
    )
    (net (code "83") (name "unconnected-(U2-~{DCD}-Pad8)") (class "Default")
      (node (ref "U2") (pin "8") (pinfunction "~{DCD}_8") (pintype "bidirectional"))
    )
    (net (code "84") (name "unconnected-(U2-~{DSR}-Pad7)") (class "Default")
      (node (ref "U2") (pin "7") (pinfunction "~{DSR}_7") (pintype "bidirectional"))
    )
    (net (code "85") (name "unconnected-(U2-~{DTR}-Pad1)") (class "Default")
      (node (ref "U2") (pin "1") (pinfunction "~{DTR}_1") (pintype "bidirectional"))
    )
    (net (code "86") (name "unconnected-(U2-~{RI}-Pad5)") (class "Default")
      (node (ref "U2") (pin "5") (pinfunction "~{RI}_5") (pintype "bidirectional"))
    )
    (net (code "87") (name "unconnected-(U2-~{RTS}-Pad2)") (class "Default")
      (node (ref "U2") (pin "2") (pinfunction "~{RTS}_2") (pintype "bidirectional"))
    )
  )
)
